# CheetahBoosterMCU.net
KiCad netlist of a schematic drawn in EAGLE
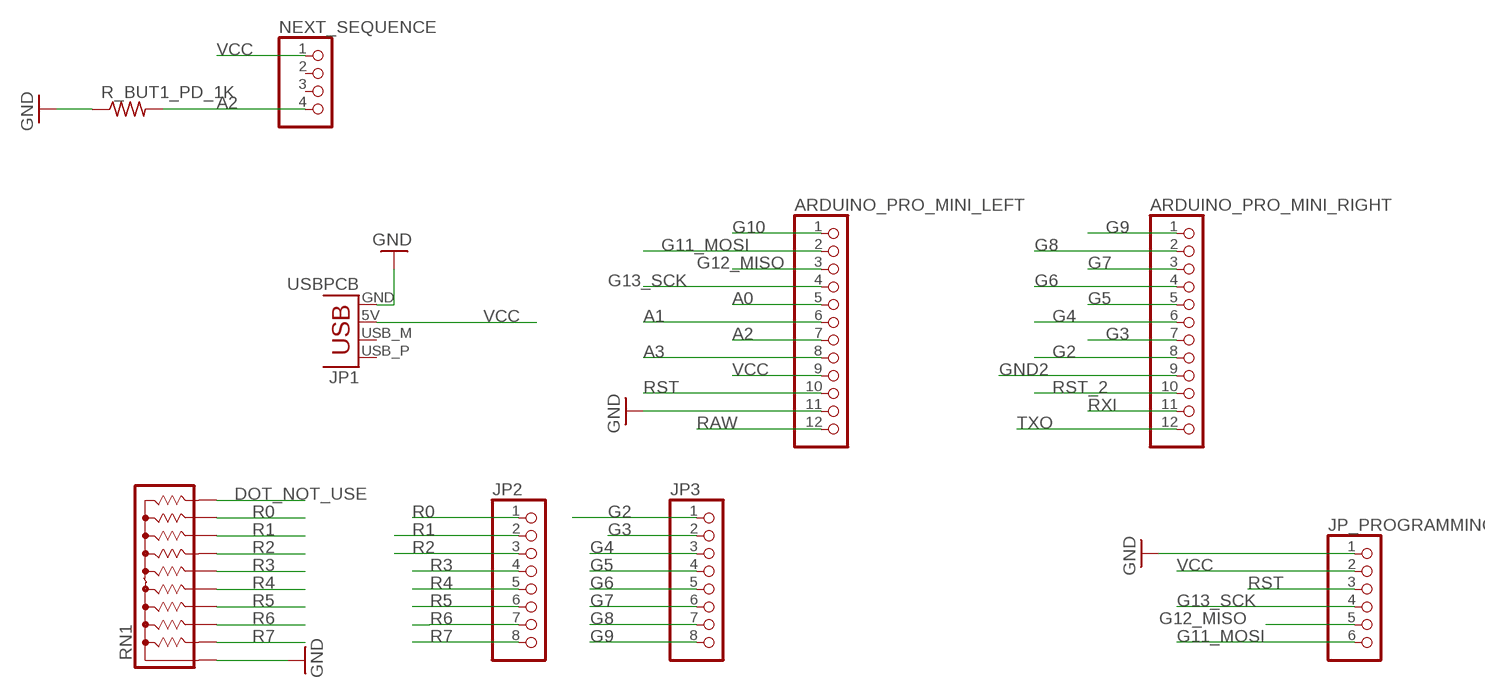
[diagram p0: schematic, sheet 1]

(export (version "E")
  (design (tool "Eeschema 10.0.6"))
  (components
    (comp (ref "ARDUINO_PRO_MINI_LEFT")
      (value "PINHD-1X12")
      (footprint "eagle-import:1X12")
      (libsource (lib "eagle-import") (part "PINHD-1X12"))
    )
    (comp (ref "ARDUINO_PRO_MINI_RIGHT")
      (value "PINHD-1X12")
      (footprint "eagle-import:1X12")
      (libsource (lib "eagle-import") (part "PINHD-1X12"))
    )
    (comp (ref "JP1")
      (value "USBPCB")
      (footprint "eagle-import:USB-A-PCB")
      (libsource (lib "eagle-import") (part "USBPCB"))
    )
    (comp (ref "JP2")
      (value "PINHD-1X8")
      (footprint "eagle-import:1X08")
      (libsource (lib "eagle-import") (part "PINHD-1X8"))
    )
    (comp (ref "JP3")
      (value "PINHD-1X8")
      (footprint "eagle-import:1X08")
      (libsource (lib "eagle-import") (part "PINHD-1X8"))
    )
    (comp (ref "JP_PROGRAMMING")
      (value "PINHD-1X6")
      (footprint "eagle-import:1X06")
      (libsource (lib "eagle-import") (part "PINHD-1X6"))
    )
    (comp (ref "NEXT_SEQUENCE")
      (value "PINHD-1X4")
      (footprint "eagle-import:1X04")
      (libsource (lib "eagle-import") (part "PINHD-1X4"))
    )
    (comp (ref "RN1")
      (value "4610X")
      (footprint "eagle-import:SIP10")
      (libsource (lib "eagle-import") (part "4610X"))
    )
    (comp (ref "R_BUT1_PD_1K")
      (value "R-US_R1206")
      (footprint "eagle-import:R1206")
      (libsource (lib "eagle-import") (part "R-US_R1206"))
    )
  )
  (nets
    (net (code "1") (name "/A0") (class "Default")
      (node (ref "ARDUINO_PRO_MINI_LEFT") (pin "5") (pinfunction "5_5") (pintype "passive"))
    )
    (net (code "2") (name "/A1") (class "Default")
      (node (ref "ARDUINO_PRO_MINI_LEFT") (pin "6") (pinfunction "6_6") (pintype "passive"))
    )
    (net (code "3") (name "/A2") (class "Default")
      (node (ref "ARDUINO_PRO_MINI_LEFT") (pin "7") (pinfunction "7_7") (pintype "passive"))
      (node (ref "NEXT_SEQUENCE") (pin "4") (pinfunction "4_4") (pintype "passive"))
      (node (ref "R_BUT1_PD_1K") (pin "2") (pinfunction "2_2") (pintype "passive"))
    )
    (net (code "4") (name "/A3") (class "Default")
      (node (ref "ARDUINO_PRO_MINI_LEFT") (pin "8") (pinfunction "8_8") (pintype "passive"))
    )
    (net (code "5") (name "/DOT_NOT_USE") (class "Default")
      (node (ref "RN1") (pin "10") (pinfunction "10_10") (pintype "passive"))
    )
    (net (code "6") (name "/G2") (class "Default")
      (node (ref "ARDUINO_PRO_MINI_RIGHT") (pin "8") (pinfunction "8_8") (pintype "passive"))
      (node (ref "JP3") (pin "1") (pinfunction "1_1") (pintype "passive"))
    )
    (net (code "7") (name "/G3") (class "Default")
      (node (ref "ARDUINO_PRO_MINI_RIGHT") (pin "7") (pinfunction "7_7") (pintype "passive"))
      (node (ref "JP3") (pin "2") (pinfunction "2_2") (pintype "passive"))
    )
    (net (code "8") (name "/G4") (class "Default")
      (node (ref "ARDUINO_PRO_MINI_RIGHT") (pin "6") (pinfunction "6_6") (pintype "passive"))
      (node (ref "JP3") (pin "3") (pinfunction "3_3") (pintype "passive"))
    )
    (net (code "9") (name "/G5") (class "Default")
      (node (ref "ARDUINO_PRO_MINI_RIGHT") (pin "5") (pinfunction "5_5") (pintype "passive"))
      (node (ref "JP3") (pin "4") (pinfunction "4_4") (pintype "passive"))
    )
    (net (code "10") (name "/G6") (class "Default")
      (node (ref "ARDUINO_PRO_MINI_RIGHT") (pin "4") (pinfunction "4_4") (pintype "passive"))
      (node (ref "JP3") (pin "5") (pinfunction "5_5") (pintype "passive"))
    )
    (net (code "11") (name "/G7") (class "Default")
      (node (ref "ARDUINO_PRO_MINI_RIGHT") (pin "3") (pinfunction "3_3") (pintype "passive"))
      (node (ref "JP3") (pin "6") (pinfunction "6_6") (pintype "passive"))
    )
    (net (code "12") (name "/G8") (class "Default")
      (node (ref "ARDUINO_PRO_MINI_RIGHT") (pin "2") (pinfunction "2_2") (pintype "passive"))
      (node (ref "JP3") (pin "7") (pinfunction "7_7") (pintype "passive"))
    )
    (net (code "13") (name "/G9") (class "Default")
      (node (ref "ARDUINO_PRO_MINI_RIGHT") (pin "1") (pinfunction "1_1") (pintype "passive"))
      (node (ref "JP3") (pin "8") (pinfunction "8_8") (pintype "passive"))
    )
    (net (code "14") (name "/G10") (class "Default")
      (node (ref "ARDUINO_PRO_MINI_LEFT") (pin "1") (pinfunction "1_1") (pintype "passive"))
    )
    (net (code "15") (name "/G11_MOSI") (class "Default")
      (node (ref "ARDUINO_PRO_MINI_LEFT") (pin "2") (pinfunction "2_2") (pintype "passive"))
      (node (ref "JP_PROGRAMMING") (pin "6") (pinfunction "6_6") (pintype "passive"))
    )
    (net (code "16") (name "/G12_MISO") (class "Default")
      (node (ref "ARDUINO_PRO_MINI_LEFT") (pin "3") (pinfunction "3_3") (pintype "passive"))
      (node (ref "JP_PROGRAMMING") (pin "5") (pinfunction "5_5") (pintype "passive"))
    )
    (net (code "17") (name "/G13_SCK") (class "Default")
      (node (ref "ARDUINO_PRO_MINI_LEFT") (pin "4") (pinfunction "4_4") (pintype "passive"))
      (node (ref "JP_PROGRAMMING") (pin "4") (pinfunction "4_4") (pintype "passive"))
    )
    (net (code "18") (name "/GND2") (class "Default")
      (node (ref "ARDUINO_PRO_MINI_RIGHT") (pin "9") (pinfunction "9_9") (pintype "passive"))
    )
    (net (code "19") (name "/R0") (class "Default")
      (node (ref "JP2") (pin "1") (pinfunction "1_1") (pintype "passive"))
      (node (ref "RN1") (pin "9") (pinfunction "9_9") (pintype "passive"))
    )
    (net (code "20") (name "/R1") (class "Default")
      (node (ref "JP2") (pin "2") (pinfunction "2_2") (pintype "passive"))
      (node (ref "RN1") (pin "8") (pinfunction "8_8") (pintype "passive"))
    )
    (net (code "21") (name "/R2") (class "Default")
      (node (ref "JP2") (pin "3") (pinfunction "3_3") (pintype "passive"))
      (node (ref "RN1") (pin "7") (pinfunction "7_7") (pintype "passive"))
    )
    (net (code "22") (name "/R3") (class "Default")
      (node (ref "JP2") (pin "4") (pinfunction "4_4") (pintype "passive"))
      (node (ref "RN1") (pin "6") (pinfunction "6_6") (pintype "passive"))
    )
    (net (code "23") (name "/R4") (class "Default")
      (node (ref "JP2") (pin "5") (pinfunction "5_5") (pintype "passive"))
      (node (ref "RN1") (pin "5") (pinfunction "5_5") (pintype "passive"))
    )
    (net (code "24") (name "/R5") (class "Default")
      (node (ref "JP2") (pin "6") (pinfunction "6_6") (pintype "passive"))
      (node (ref "RN1") (pin "4") (pinfunction "4_4") (pintype "passive"))
    )
    (net (code "25") (name "/R6") (class "Default")
      (node (ref "JP2") (pin "7") (pinfunction "7_7") (pintype "passive"))
      (node (ref "RN1") (pin "3") (pinfunction "3_3") (pintype "passive"))
    )
    (net (code "26") (name "/R7") (class "Default")
      (node (ref "JP2") (pin "8") (pinfunction "8_8") (pintype "passive"))
      (node (ref "RN1") (pin "2") (pinfunction "2_2") (pintype "passive"))
    )
    (net (code "27") (name "/RAW") (class "Default")
      (node (ref "ARDUINO_PRO_MINI_LEFT") (pin "12") (pinfunction "12_12") (pintype "passive"))
    )
    (net (code "28") (name "/RST") (class "Default")
      (node (ref "ARDUINO_PRO_MINI_LEFT") (pin "10") (pinfunction "10_10") (pintype "passive"))
      (node (ref "JP_PROGRAMMING") (pin "3") (pinfunction "3_3") (pintype "passive"))
    )
    (net (code "29") (name "/RST_2") (class "Default")
      (node (ref "ARDUINO_PRO_MINI_RIGHT") (pin "10") (pinfunction "10_10") (pintype "passive"))
    )
    (net (code "30") (name "/RXI") (class "Default")
      (node (ref "ARDUINO_PRO_MINI_RIGHT") (pin "11") (pinfunction "11_11") (pintype "passive"))
    )
    (net (code "31") (name "/TXO") (class "Default")
      (node (ref "ARDUINO_PRO_MINI_RIGHT") (pin "12") (pinfunction "12_12") (pintype "passive"))
    )
    (net (code "32") (name "/VCC") (class "Default")
      (node (ref "ARDUINO_PRO_MINI_LEFT") (pin "9") (pinfunction "9_9") (pintype "passive"))
      (node (ref "JP1") (pin "5V") (pinfunction "VBUS_5V") (pintype "bidirectional"))
      (node (ref "JP_PROGRAMMING") (pin "2") (pinfunction "2_2") (pintype "passive"))
      (node (ref "NEXT_SEQUENCE") (pin "1") (pinfunction "1_1") (pintype "passive"))
    )
    (net (code "33") (name "GND") (class "Default")
      (node (ref "ARDUINO_PRO_MINI_LEFT") (pin "11") (pinfunction "11_11") (pintype "passive"))
      (node (ref "JP1") (pin "GND") (pinfunction "GND_GND") (pintype "bidirectional"))
      (node (ref "JP_PROGRAMMING") (pin "1") (pinfunction "1_1") (pintype "passive"))
      (node (ref "RN1") (pin "1") (pinfunction "1_1") (pintype "passive"))
      (node (ref "R_BUT1_PD_1K") (pin "1") (pinfunction "1_1") (pintype "passive"))
    )
    (net (code "34") (name "unconnected-(JP1-D+-PadUSB_P)") (class "Default")
      (node (ref "JP1") (pin "USB_P") (pinfunction "D+_USB_P") (pintype "bidirectional"))
    )
    (net (code "35") (name "unconnected-(JP1-D--PadUSB_M)") (class "Default")
      (node (ref "JP1") (pin "USB_M") (pinfunction "D-_USB_M") (pintype "bidirectional"))
    )
    (net (code "36") (name "unconnected-(NEXT_SEQUENCE-Pad2)") (class "Default")
      (node (ref "NEXT_SEQUENCE") (pin "2") (pinfunction "2_2") (pintype "passive"))
    )
    (net (code "37") (name "unconnected-(NEXT_SEQUENCE-Pad3)") (class "Default")
      (node (ref "NEXT_SEQUENCE") (pin "3") (pinfunction "3_3") (pintype "passive"))
    )
  )
)
